# Grove_-_Temperature_Humidity_Sensor_HDC1.net
KiCad netlist of a schematic drawn in EAGLE
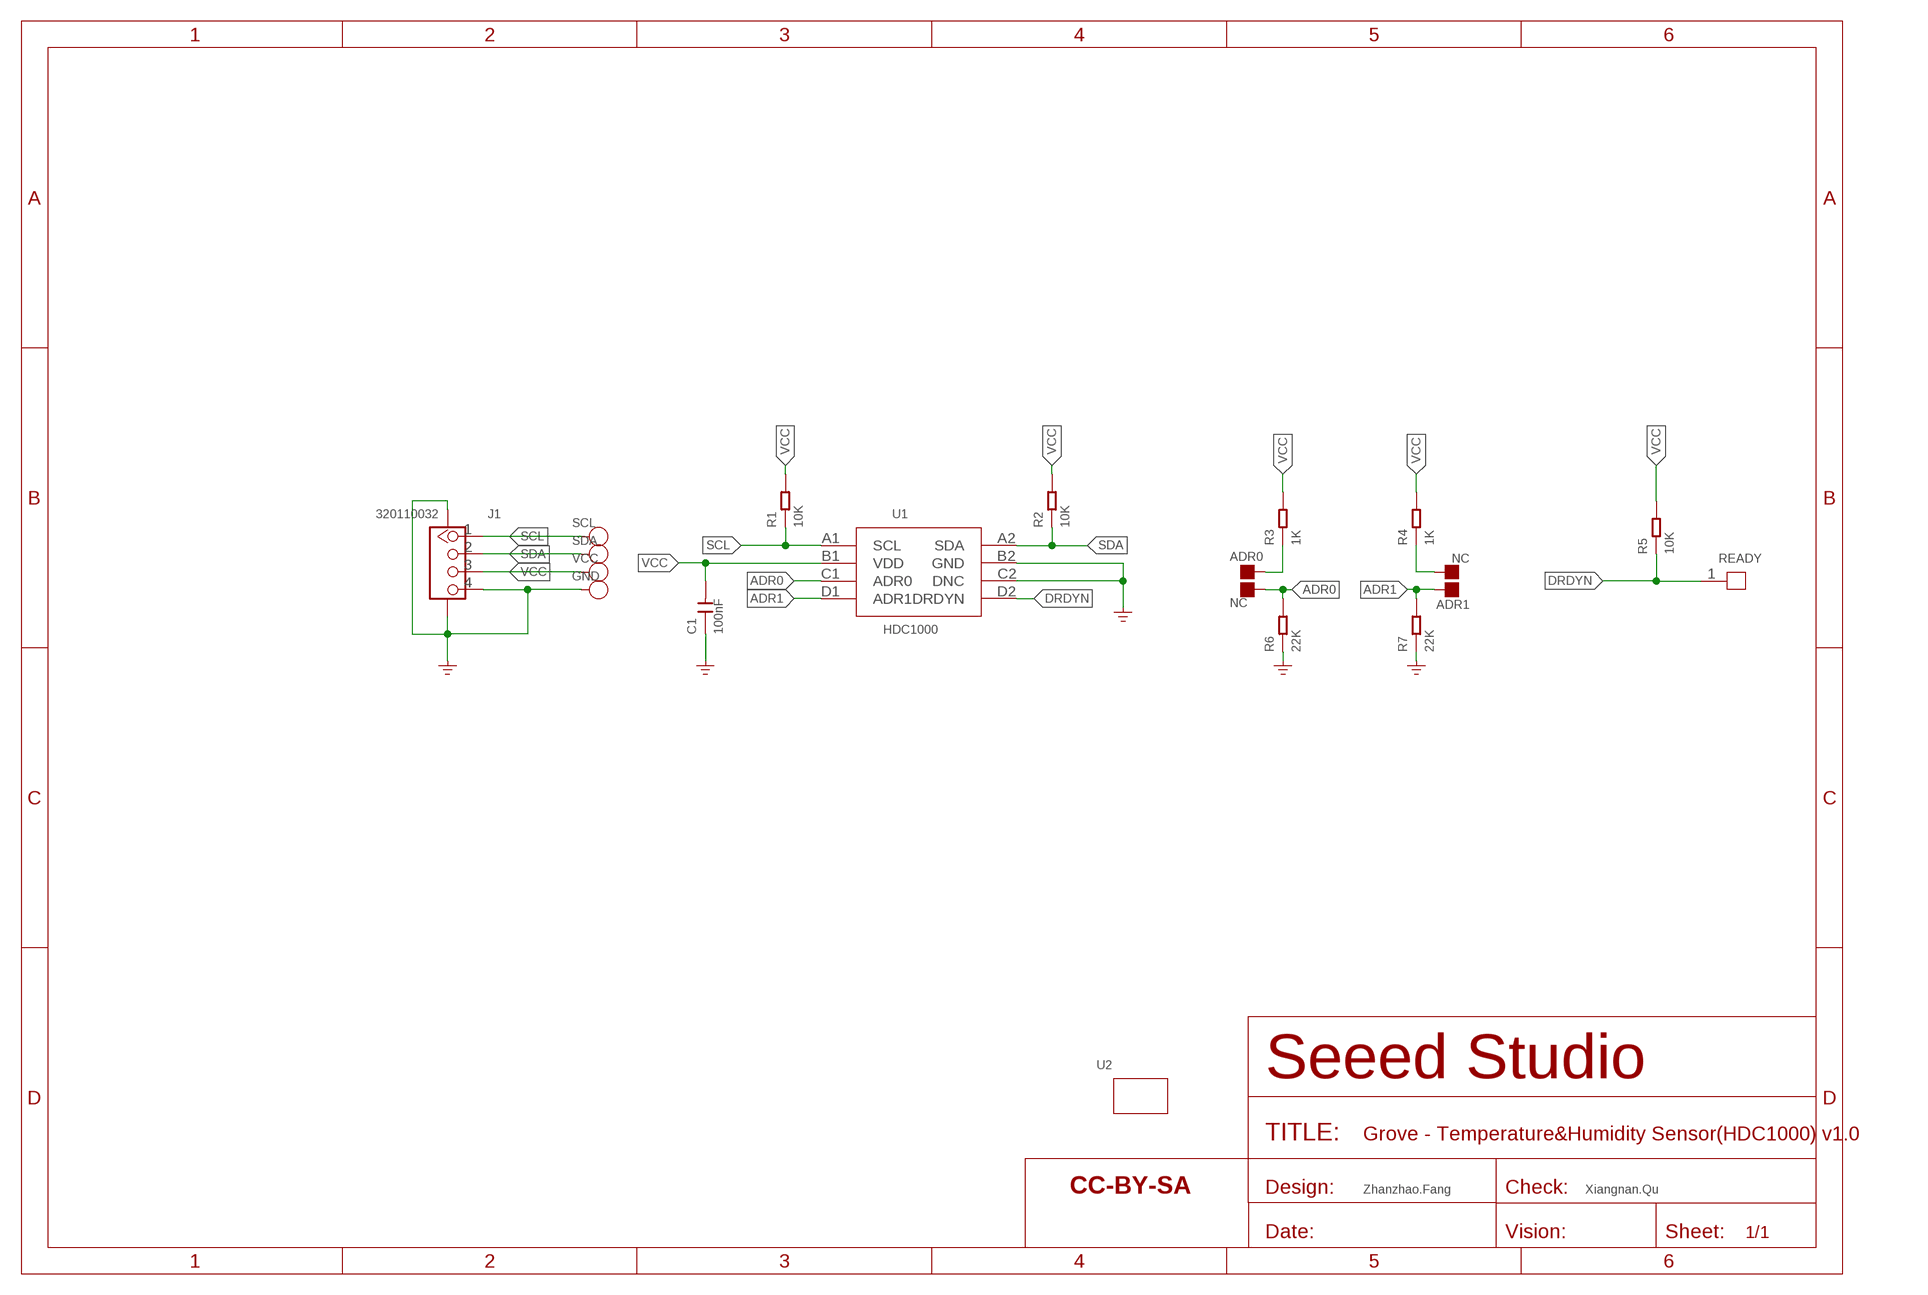
[diagram p0: schematic, sheet 1]

(export (version "E")
  (design (tool "Eeschema 10.0.6"))
  (components
    (comp (ref "ADR0")
      (value "NC")
      (footprint "eagle-import:JUMPER-2P")
      (fields (field (name "PARTNO") "DNP"))
      (libsource (lib "eagle-import") (part "JUMPER-2P"))
    )
    (comp (ref "ADR1")
      (value "NC")
      (footprint "eagle-import:JUMPER-2P")
      (fields (field (name "PARTNO") "DNP"))
      (libsource (lib "eagle-import") (part "JUMPER-2P"))
    )
    (comp (ref "C1")
      (value "100nF")
      (footprint "eagle-import:C0603")
      (libsource (lib "eagle-import") (part "CAP-0603"))
    )
    (comp (ref "GND")
      (value "NC")
      (footprint "eagle-import:TP-D45MIL")
      (fields (field (name "PARTNO") "DNP"))
      (libsource (lib "eagle-import") (part "TEST-POINT'4545'"))
    )
    (comp (ref "J1")
      (value "320110032")
      (footprint "eagle-import:HW4-SMD-2.0-90D")
      (libsource (lib "eagle-import") (part "GROVE-CONNECTOR-SMD'90D'"))
    )
    (comp (ref "R1")
      (value "10K")
      (footprint "eagle-import:R0603")
      (libsource (lib "eagle-import") (part "RES-0603"))
    )
    (comp (ref "R2")
      (value "10K")
      (footprint "eagle-import:R0603")
      (libsource (lib "eagle-import") (part "RES-0603"))
    )
    (comp (ref "R3")
      (value "1K")
      (footprint "eagle-import:R0603")
      (libsource (lib "eagle-import") (part "RES-0603"))
    )
    (comp (ref "R4")
      (value "1K")
      (footprint "eagle-import:R0603")
      (libsource (lib "eagle-import") (part "RES-0603"))
    )
    (comp (ref "R5")
      (value "10K")
      (footprint "eagle-import:R0603")
      (libsource (lib "eagle-import") (part "RES-0603"))
    )
    (comp (ref "R6")
      (value "22K")
      (footprint "eagle-import:R0603")
      (libsource (lib "eagle-import") (part "RES-0603"))
    )
    (comp (ref "R7")
      (value "22K")
      (footprint "eagle-import:R0603")
      (libsource (lib "eagle-import") (part "RES-0603"))
    )
    (comp (ref "READY")
      (value "HEADER-1P-40")
      (footprint "eagle-import:1P-80_40MIL")
      (libsource (lib "eagle-import") (part "HEADER-1P-40"))
    )
    (comp (ref "SCL")
      (value "NC")
      (footprint "eagle-import:TP-D45MIL")
      (fields (field (name "PARTNO") "DNP"))
      (libsource (lib "eagle-import") (part "TEST-POINT'4545'"))
    )
    (comp (ref "SDA")
      (value "NC")
      (footprint "eagle-import:TP-D45MIL")
      (fields (field (name "PARTNO") "DNP"))
      (libsource (lib "eagle-import") (part "TEST-POINT'4545'"))
    )
    (comp (ref "U$4")
      (value "SEEEDSTUDIO-OPEN-SCH-FRAME")
      (footprint "eagle-import:SEEEDSTUDIO-PCB-FRAME")
      (libsource (lib "eagle-import") (part "SEEEDSTUDIO-OPEN-SCH-FRAME"))
    )
    (comp (ref "U1")
      (value "HDC1000")
      (footprint "eagle-import:SNR8-SMD-0.5-2.04X1.59MM")
      (libsource (lib "eagle-import") (part "SENSOR-HDC1000"))
    )
    (comp (ref "U2")
      (value "GROVE'2U'")
      (footprint "eagle-import:GROVE-1_2-TEST-PLATFORM")
      (libsource (lib "eagle-import") (part "GROVE'2U'"))
    )
    (comp (ref "VCC")
      (value "NC")
      (footprint "eagle-import:TP-D45MIL")
      (fields (field (name "PARTNO") "DNP"))
      (libsource (lib "eagle-import") (part "TEST-POINT'4545'"))
    )
  )
  (nets
    (net (code "1") (name "ADR0") (class "Default")
      (node (ref "ADR0") (pin "1") (pinfunction "1_1") (pintype "bidirectional"))
      (node (ref "R6") (pin "2") (pinfunction "2_2") (pintype "passive"))
      (node (ref "U1") (pin "C1") (pinfunction "ADR0_C1") (pintype "bidirectional"))
    )
    (net (code "2") (name "ADR1") (class "Default")
      (node (ref "ADR1") (pin "2") (pinfunction "2_2") (pintype "bidirectional"))
      (node (ref "R7") (pin "2") (pinfunction "2_2") (pintype "passive"))
      (node (ref "U1") (pin "D1") (pinfunction "ADR1_D1") (pintype "bidirectional"))
    )
    (net (code "3") (name "DRDYN") (class "Default")
      (node (ref "R5") (pin "1") (pinfunction "1_1") (pintype "passive"))
      (node (ref "READY") (pin "1") (pinfunction "1_1") (pintype "bidirectional"))
      (node (ref "U1") (pin "D2") (pinfunction "DRDYN_D2") (pintype "bidirectional"))
    )
    (net (code "4") (name "GND_POWER") (class "Default")
      (node (ref "C1") (pin "1") (pinfunction "1_1") (pintype "passive"))
      (node (ref "GND") (pin "T") (pinfunction "T_T") (pintype "bidirectional"))
      (node (ref "J1") (pin "4") (pinfunction "4_4") (pintype "bidirectional"))
      (node (ref "J1") (pin "SS1") (pinfunction "SS1_SS1") (pintype "bidirectional"))
      (node (ref "J1") (pin "SS2") (pinfunction "SS2_SS2") (pintype "bidirectional"))
      (node (ref "R6") (pin "1") (pinfunction "1_1") (pintype "passive"))
      (node (ref "R7") (pin "1") (pinfunction "1_1") (pintype "passive"))
      (node (ref "U1") (pin "B2") (pinfunction "GND_B2") (pintype "bidirectional"))
      (node (ref "U1") (pin "C2") (pinfunction "DNC_C2") (pintype "bidirectional"))
    )
    (net (code "5") (name "Net-(ADR0-Pad2)") (class "Default")
      (node (ref "ADR0") (pin "2") (pinfunction "2_2") (pintype "bidirectional"))
      (node (ref "R3") (pin "1") (pinfunction "1_1") (pintype "passive"))
    )
    (net (code "6") (name "Net-(ADR1-Pad1)") (class "Default")
      (node (ref "ADR1") (pin "1") (pinfunction "1_1") (pintype "bidirectional"))
      (node (ref "R4") (pin "1") (pinfunction "1_1") (pintype "passive"))
    )
    (net (code "7") (name "SCL") (class "Default")
      (node (ref "J1") (pin "1") (pinfunction "1_1") (pintype "bidirectional"))
      (node (ref "R1") (pin "1") (pinfunction "1_1") (pintype "passive"))
      (node (ref "SCL") (pin "T") (pinfunction "T_T") (pintype "bidirectional"))
      (node (ref "U1") (pin "A1") (pinfunction "SCL_A1") (pintype "bidirectional"))
    )
    (net (code "8") (name "SDA") (class "Default")
      (node (ref "J1") (pin "2") (pinfunction "2_2") (pintype "bidirectional"))
      (node (ref "R2") (pin "1") (pinfunction "1_1") (pintype "passive"))
      (node (ref "SDA") (pin "T") (pinfunction "T_T") (pintype "bidirectional"))
      (node (ref "U1") (pin "A2") (pinfunction "SDA_A2") (pintype "bidirectional"))
    )
    (net (code "9") (name "VCC") (class "Default")
      (node (ref "C1") (pin "2") (pinfunction "2_2") (pintype "passive"))
      (node (ref "J1") (pin "3") (pinfunction "3_3") (pintype "bidirectional"))
      (node (ref "R1") (pin "2") (pinfunction "2_2") (pintype "passive"))
      (node (ref "R2") (pin "2") (pinfunction "2_2") (pintype "passive"))
      (node (ref "R3") (pin "2") (pinfunction "2_2") (pintype "passive"))
      (node (ref "R4") (pin "2") (pinfunction "2_2") (pintype "passive"))
      (node (ref "R5") (pin "2") (pinfunction "2_2") (pintype "passive"))
      (node (ref "U1") (pin "B1") (pinfunction "VDD_B1") (pintype "bidirectional"))
      (node (ref "VCC") (pin "T") (pinfunction "T_T") (pintype "bidirectional"))
    )
  )
)
